# Simple_Project.net
KiCad netlist of a schematic drawn in Altium Designer
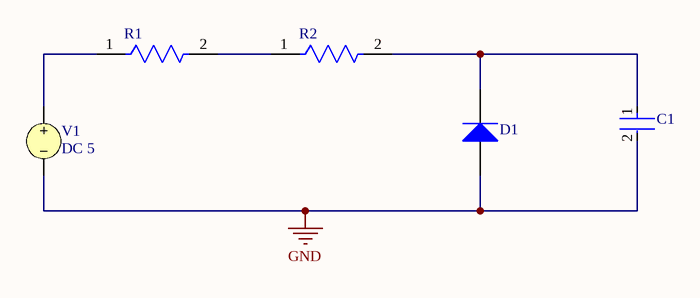
[diagram p0: Simple_Project.SchDoc]

(export (version "E")
  (design (tool "Eeschema 10.0.6"))
  (components
    (comp (ref "C1")
      (value "GRM188R60J106ME47D")
      (footprint "FP-GRM188-0_1-e0_2_0_55-IPC_A")
      (description "Chip Multilayer Ceramic Capacitors for General Purpose, 0603, 10uF, X5R, 15%, 20%, 6.3V")
      (fields (field (name "VOLTAGE") "6.3V") (field (name "TOLERANCE") "20%"))
      (libsource (lib "Altium Content Vault") (part "02cd4be3c70576c341d710602a673aa"))
    )
    (comp (ref "D1")
      (value "FDLL4148")
      (footprint "FAIR-LL-34_V")
      (description "High Conductance Fast Diode, 500 mW, 100 V, -65 to 175 degC, 2-Pin SMD, RoHS, Tape and Reel")
      (fields (field (name "MANUFACTURER") "FairchildSemiconductor"))
      (libsource (lib "Altium Content Vault") (part "D-AK-2"))
    )
    (comp (ref "R1")
      (value "MRS25000C1001FCT00")
      (footprint "FP-MRS25-MFG")
      (description "RES 1K OHM 0.6W 1% AXIAL")
      (fields (field (name "TOLERANCE") "1%"))
      (libsource (lib "Altium Content Vault") (part "1029c3af85768c4190bb7ad29bc67b5"))
    )
    (comp (ref "R2")
      (value "MRS25000C1001FCT00")
      (footprint "FP-MRS25-MFG")
      (description "RES 1K OHM 0.6W 1% AXIAL")
      (fields (field (name "TOLERANCE") "1%"))
      (libsource (lib "Altium Content Vault") (part "1029c3af85768c4190bb7ad29bc67b5"))
    )
    (comp (ref "V1")
      (value "DC 5")
      (description "Voltage Source")
      (fields (field (name "PUBLISHER") "Altium Limited"))
      (libsource (lib "Simulation Generic Components") (part "VSRC"))
    )
  )
  (nets
    (net (code "1") (name "GND") (class "Default")
      (node (ref "C1") (pin "2") (pinfunction "2_2") (pintype "passive"))
      (node (ref "D1") (pin "1") (pinfunction "A_1") (pintype "passive"))
      (node (ref "V1") (pin "2") (pinfunction "2_2") (pintype "passive"))
    )
    (net (code "2") (name "Net-(D1-K)") (class "Default")
      (node (ref "C1") (pin "1") (pinfunction "1_1") (pintype "passive"))
      (node (ref "D1") (pin "2") (pinfunction "K_2") (pintype "passive"))
      (node (ref "R2") (pin "2") (pinfunction "2_2") (pintype "passive"))
    )
    (net (code "3") (name "Net-(R1-Pad1)") (class "Default")
      (node (ref "R1") (pin "1") (pinfunction "1_1") (pintype "passive"))
      (node (ref "V1") (pin "1") (pinfunction "1_1") (pintype "passive"))
    )
    (net (code "4") (name "Net-(R1-Pad2)") (class "Default")
      (node (ref "R1") (pin "2") (pinfunction "2_2") (pintype "passive"))
      (node (ref "R2") (pin "1") (pinfunction "1_1") (pintype "passive"))
    )
  )
)
